# zza.net
KiCad netlist of a schematic drawn in EAGLE
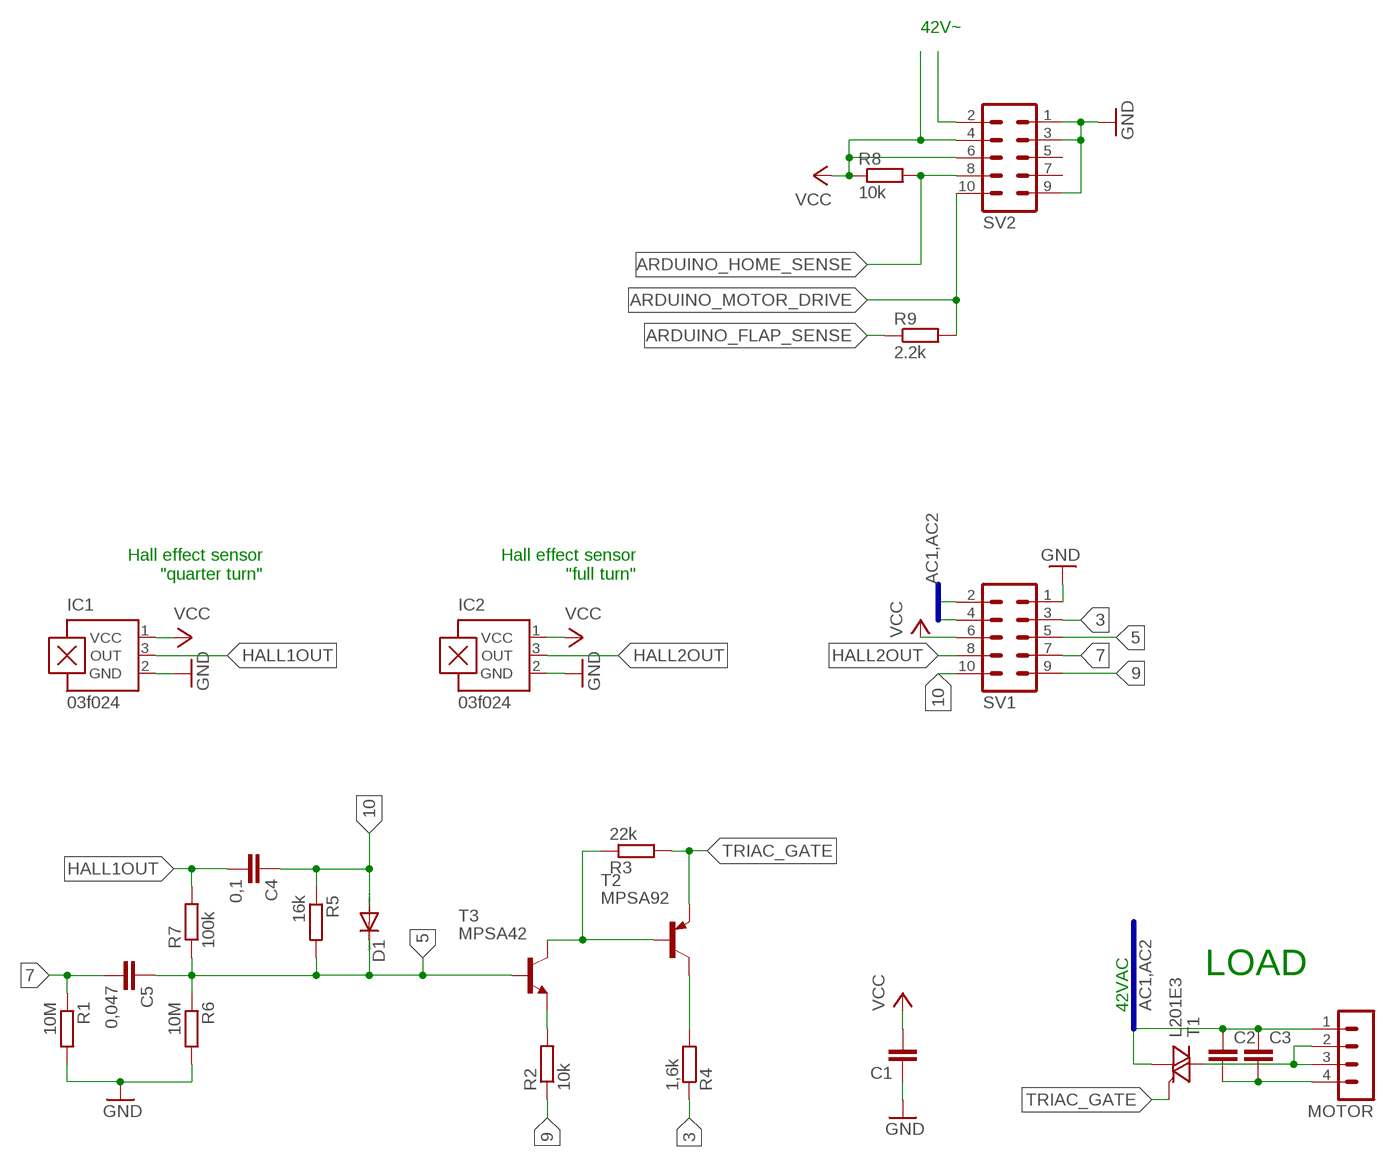
[diagram p0: schematic, sheet 1]

(export (version "E")
  (design (tool "Eeschema 10.0.6"))
  (components
    (comp (ref "C1")
      (value "C-EU025-024X044")
      (footprint "eagle-import:C025-024X044")
      (libsource (lib "eagle-import") (part "C-EU025-024X044"))
    )
    (comp (ref "C2")
      (value "C-EU375-155X418")
      (footprint "eagle-import:C375-155X418")
      (libsource (lib "eagle-import") (part "C-EU375-155X418"))
    )
    (comp (ref "C3")
      (value "C-EU075-052X106")
      (footprint "eagle-import:C075-052X106")
      (libsource (lib "eagle-import") (part "C-EU075-052X106"))
    )
    (comp (ref "C4")
      (value "0,1")
      (footprint "eagle-import:C025-024X044")
      (libsource (lib "eagle-import") (part "C-EU025-024X044"))
    )
    (comp (ref "C5")
      (value "0,047")
      (footprint "eagle-import:C025-024X044")
      (libsource (lib "eagle-import") (part "C-EU025-024X044"))
    )
    (comp (ref "D1")
      (value "1N4004")
      (footprint "eagle-import:DO41-10")
      (libsource (lib "eagle-import") (part "1N4004"))
    )
    (comp (ref "IC1")
      (value "03f024")
      (footprint "eagle-import:SIP3-UA")
      (fields (field (name "MF") "ALLEGRO MICROSYSTEMS, INC.") (field (name "MPN") "A1301EUA-T"))
      (libsource (lib "eagle-import") (part "A13?UA01"))
    )
    (comp (ref "IC2")
      (value "03f024")
      (footprint "eagle-import:SIP3-UA")
      (fields (field (name "MF") "ALLEGRO MICROSYSTEMS, INC.") (field (name "MPN") "A1301EUA-T"))
      (libsource (lib "eagle-import") (part "A13?UA01"))
    )
    (comp (ref "MOTOR")
      (value "MA04-1")
      (footprint "eagle-import:MA04-1")
      (libsource (lib "eagle-import") (part "MA04-1"))
    )
    (comp (ref "R1")
      (value "10M")
      (footprint "eagle-import:0207_10")
      (libsource (lib "eagle-import") (part "R-EU_0207/10"))
    )
    (comp (ref "R2")
      (value "10k")
      (footprint "eagle-import:0207_10")
      (libsource (lib "eagle-import") (part "R-EU_0207/10"))
    )
    (comp (ref "R3")
      (value "22k")
      (footprint "eagle-import:0207_10")
      (libsource (lib "eagle-import") (part "R-EU_0207/10"))
    )
    (comp (ref "R4")
      (value "1,6k")
      (footprint "eagle-import:0207_10")
      (libsource (lib "eagle-import") (part "R-EU_0207/10"))
    )
    (comp (ref "R5")
      (value "16k")
      (footprint "eagle-import:0207_10")
      (libsource (lib "eagle-import") (part "R-EU_0207/10"))
    )
    (comp (ref "R6")
      (value "10M")
      (footprint "eagle-import:0207_10")
      (libsource (lib "eagle-import") (part "R-EU_0207/10"))
    )
    (comp (ref "R7")
      (value "100k")
      (footprint "eagle-import:0207_10")
      (libsource (lib "eagle-import") (part "R-EU_0207/10"))
    )
    (comp (ref "R8")
      (value "10k")
      (footprint "eagle-import:0204V")
      (libsource (lib "eagle-import") (part "R-EU_0204/2V"))
    )
    (comp (ref "R9")
      (value "2.2k")
      (footprint "eagle-import:0204V")
      (libsource (lib "eagle-import") (part "R-EU_0204/2V"))
    )
    (comp (ref "SV1")
      (value "MA05-2")
      (footprint "eagle-import:MA05-2")
      (libsource (lib "eagle-import") (part "MA05-2"))
    )
    (comp (ref "SV2")
      (value "MA05-2")
      (footprint "eagle-import:MA05-2")
      (libsource (lib "eagle-import") (part "MA05-2"))
    )
    (comp (ref "T1")
      (value "L201E3")
      (footprint "eagle-import:TO220BV")
      (libsource (lib "eagle-import") (part "BT138-V"))
    )
    (comp (ref "T2")
      (value "MPSA92")
      (footprint "eagle-import:TO92-EBC")
      (libsource (lib "eagle-import") (part "-PNP-TO92-EBCMPSA92"))
    )
    (comp (ref "T3")
      (value "MPSA42")
      (footprint "eagle-import:TO92-EBC")
      (libsource (lib "eagle-import") (part "-NPN-TO92-EBCMPSA42"))
    )
  )
  (nets
    (net (code "1") (name "/AC1") (class "Default")
      (node (ref "SV1") (pin "4") (pinfunction "4_4") (pintype "passive"))
      (node (ref "T1") (pin "T1") (pinfunction "A1_T1") (pintype "passive"))
    )
    (net (code "2") (name "/AC2") (class "Default")
      (node (ref "C2") (pin "1") (pinfunction "1_1") (pintype "passive"))
      (node (ref "C3") (pin "1") (pinfunction "1_1") (pintype "passive"))
      (node (ref "MOTOR") (pin "1") (pinfunction "1_1") (pintype "passive"))
      (node (ref "SV1") (pin "2") (pinfunction "2_2") (pintype "passive"))
    )
    (net (code "4") (name "3") (class "Default")
      (node (ref "R4") (pin "1") (pinfunction "1_1") (pintype "passive"))
      (node (ref "SV1") (pin "3") (pinfunction "3_3") (pintype "passive"))
    )
    (net (code "5") (name "5") (class "Default")
      (node (ref "C5") (pin "1") (pinfunction "1_1") (pintype "passive"))
      (node (ref "D1") (pin "C") (pinfunction "C_C") (pintype "passive"))
      (node (ref "R5") (pin "2") (pinfunction "2_2") (pintype "passive"))
      (node (ref "R6") (pin "1") (pinfunction "1_1") (pintype "passive"))
      (node (ref "R7") (pin "1") (pinfunction "1_1") (pintype "passive"))
      (node (ref "SV1") (pin "5") (pinfunction "5_5") (pintype "passive"))
      (node (ref "T3") (pin "B") (pinfunction "B_B") (pintype "passive"))
    )
    (net (code "6") (name "7") (class "Default")
      (node (ref "C5") (pin "2") (pinfunction "2_2") (pintype "passive"))
      (node (ref "R1") (pin "1") (pinfunction "1_1") (pintype "passive"))
      (node (ref "SV1") (pin "7") (pinfunction "7_7") (pintype "passive"))
    )
    (net (code "7") (name "9") (class "Default")
      (node (ref "R2") (pin "1") (pinfunction "1_1") (pintype "passive"))
      (node (ref "SV1") (pin "9") (pinfunction "9_9") (pintype "passive"))
    )
    (net (code "8") (name "10") (class "Default")
      (node (ref "C4") (pin "1") (pinfunction "1_1") (pintype "passive"))
      (node (ref "D1") (pin "A") (pinfunction "A_A") (pintype "passive"))
      (node (ref "R5") (pin "1") (pinfunction "1_1") (pintype "passive"))
      (node (ref "SV1") (pin "10") (pinfunction "10_10") (pintype "passive"))
    )
    (net (code "9") (name "ARDUINO_FLAP_SENSE") (class "Default")
      (node (ref "R9") (pin "1") (pinfunction "1_1") (pintype "passive"))
    )
    (net (code "10") (name "ARDUINO_HOME_SENSE") (class "Default")
      (node (ref "R8") (pin "2") (pinfunction "2_2") (pintype "passive"))
      (node (ref "SV2") (pin "8") (pinfunction "8_8") (pintype "passive"))
    )
    (net (code "11") (name "ARDUINO_MOTOR_DRIVE") (class "Default")
      (node (ref "R9") (pin "2") (pinfunction "2_2") (pintype "passive"))
      (node (ref "SV2") (pin "10") (pinfunction "10_10") (pintype "passive"))
    )
    (net (code "12") (name "GND") (class "Default")
      (node (ref "C1") (pin "1") (pinfunction "1_1") (pintype "passive"))
      (node (ref "IC1") (pin "2") (pinfunction "GND_2") (pintype "power_in"))
      (node (ref "IC2") (pin "2") (pinfunction "GND_2") (pintype "power_in"))
      (node (ref "R1") (pin "2") (pinfunction "2_2") (pintype "passive"))
      (node (ref "R6") (pin "2") (pinfunction "2_2") (pintype "passive"))
      (node (ref "SV1") (pin "1") (pinfunction "1_1") (pintype "passive"))
      (node (ref "SV2") (pin "1") (pinfunction "1_1") (pintype "passive"))
      (node (ref "SV2") (pin "3") (pinfunction "3_3") (pintype "passive"))
      (node (ref "SV2") (pin "9") (pinfunction "9_9") (pintype "passive"))
    )
    (net (code "13") (name "HALL1OUT") (class "Default")
      (node (ref "C4") (pin "2") (pinfunction "2_2") (pintype "passive"))
      (node (ref "IC1") (pin "3") (pinfunction "OUT_3") (pintype "output"))
      (node (ref "R7") (pin "2") (pinfunction "2_2") (pintype "passive"))
    )
    (net (code "14") (name "HALL2OUT") (class "Default")
      (node (ref "IC2") (pin "3") (pinfunction "OUT_3") (pintype "output"))
      (node (ref "SV1") (pin "8") (pinfunction "8_8") (pintype "passive"))
    )
    (net (code "15") (name "Net-(C2-Pad2)") (class "Default")
      (node (ref "C2") (pin "2") (pinfunction "2_2") (pintype "passive"))
      (node (ref "C3") (pin "2") (pinfunction "2_2") (pintype "passive"))
      (node (ref "MOTOR") (pin "4") (pinfunction "4_4") (pintype "passive"))
    )
    (net (code "16") (name "Net-(R2-Pad2)") (class "Default")
      (node (ref "R2") (pin "2") (pinfunction "2_2") (pintype "passive"))
      (node (ref "T3") (pin "E") (pinfunction "E_E") (pintype "passive"))
    )
    (net (code "17") (name "Net-(R3-Pad1)") (class "Default")
      (node (ref "R3") (pin "1") (pinfunction "1_1") (pintype "passive"))
      (node (ref "T2") (pin "B") (pinfunction "B_B") (pintype "passive"))
      (node (ref "T3") (pin "C") (pinfunction "C_C") (pintype "passive"))
    )
    (net (code "18") (name "Net-(R4-Pad2)") (class "Default")
      (node (ref "R4") (pin "2") (pinfunction "2_2") (pintype "passive"))
      (node (ref "T2") (pin "C") (pinfunction "C_C") (pintype "passive"))
    )
    (net (code "19") (name "Net-(T1-A2)") (class "Default")
      (node (ref "MOTOR") (pin "2") (pinfunction "2_2") (pintype "passive"))
      (node (ref "MOTOR") (pin "3") (pinfunction "3_3") (pintype "passive"))
      (node (ref "T1") (pin "T2") (pinfunction "A2_T2") (pintype "passive"))
    )
    (net (code "20") (name "TRIAC_GATE") (class "Default")
      (node (ref "R3") (pin "2") (pinfunction "2_2") (pintype "passive"))
      (node (ref "T2") (pin "E") (pinfunction "E_E") (pintype "passive"))
    )
    (net (code "21") (name "VCC") (class "Default")
      (node (ref "C1") (pin "2") (pinfunction "2_2") (pintype "passive"))
      (node (ref "IC1") (pin "1") (pinfunction "VCC_1") (pintype "power_in"))
      (node (ref "IC2") (pin "1") (pinfunction "VCC_1") (pintype "power_in"))
      (node (ref "R8") (pin "1") (pinfunction "1_1") (pintype "passive"))
      (node (ref "SV1") (pin "6") (pinfunction "6_6") (pintype "passive"))
      (node (ref "SV2") (pin "4") (pinfunction "4_4") (pintype "passive"))
      (node (ref "SV2") (pin "6") (pinfunction "6_6") (pintype "passive"))
    )
    (net (code "22") (name "unconnected-(SV2-Pad2)") (class "Default")
      (node (ref "SV2") (pin "2") (pinfunction "2_2") (pintype "passive"))
    )
    (net (code "23") (name "unconnected-(SV2-Pad5)") (class "Default")
      (node (ref "SV2") (pin "5") (pinfunction "5_5") (pintype "passive"))
    )
    (net (code "24") (name "unconnected-(SV2-Pad7)") (class "Default")
      (node (ref "SV2") (pin "7") (pinfunction "7_7") (pintype "passive"))
    )
    (net (code "25") (name "unconnected-(T1-PadG)") (class "Default")
      (node (ref "T1") (pin "G") (pinfunction "G_G") (pintype "passive"))
    )
  )
)
